# RS485_RS232_Sheet.net
KiCad netlist of a schematic drawn in Altium Designer
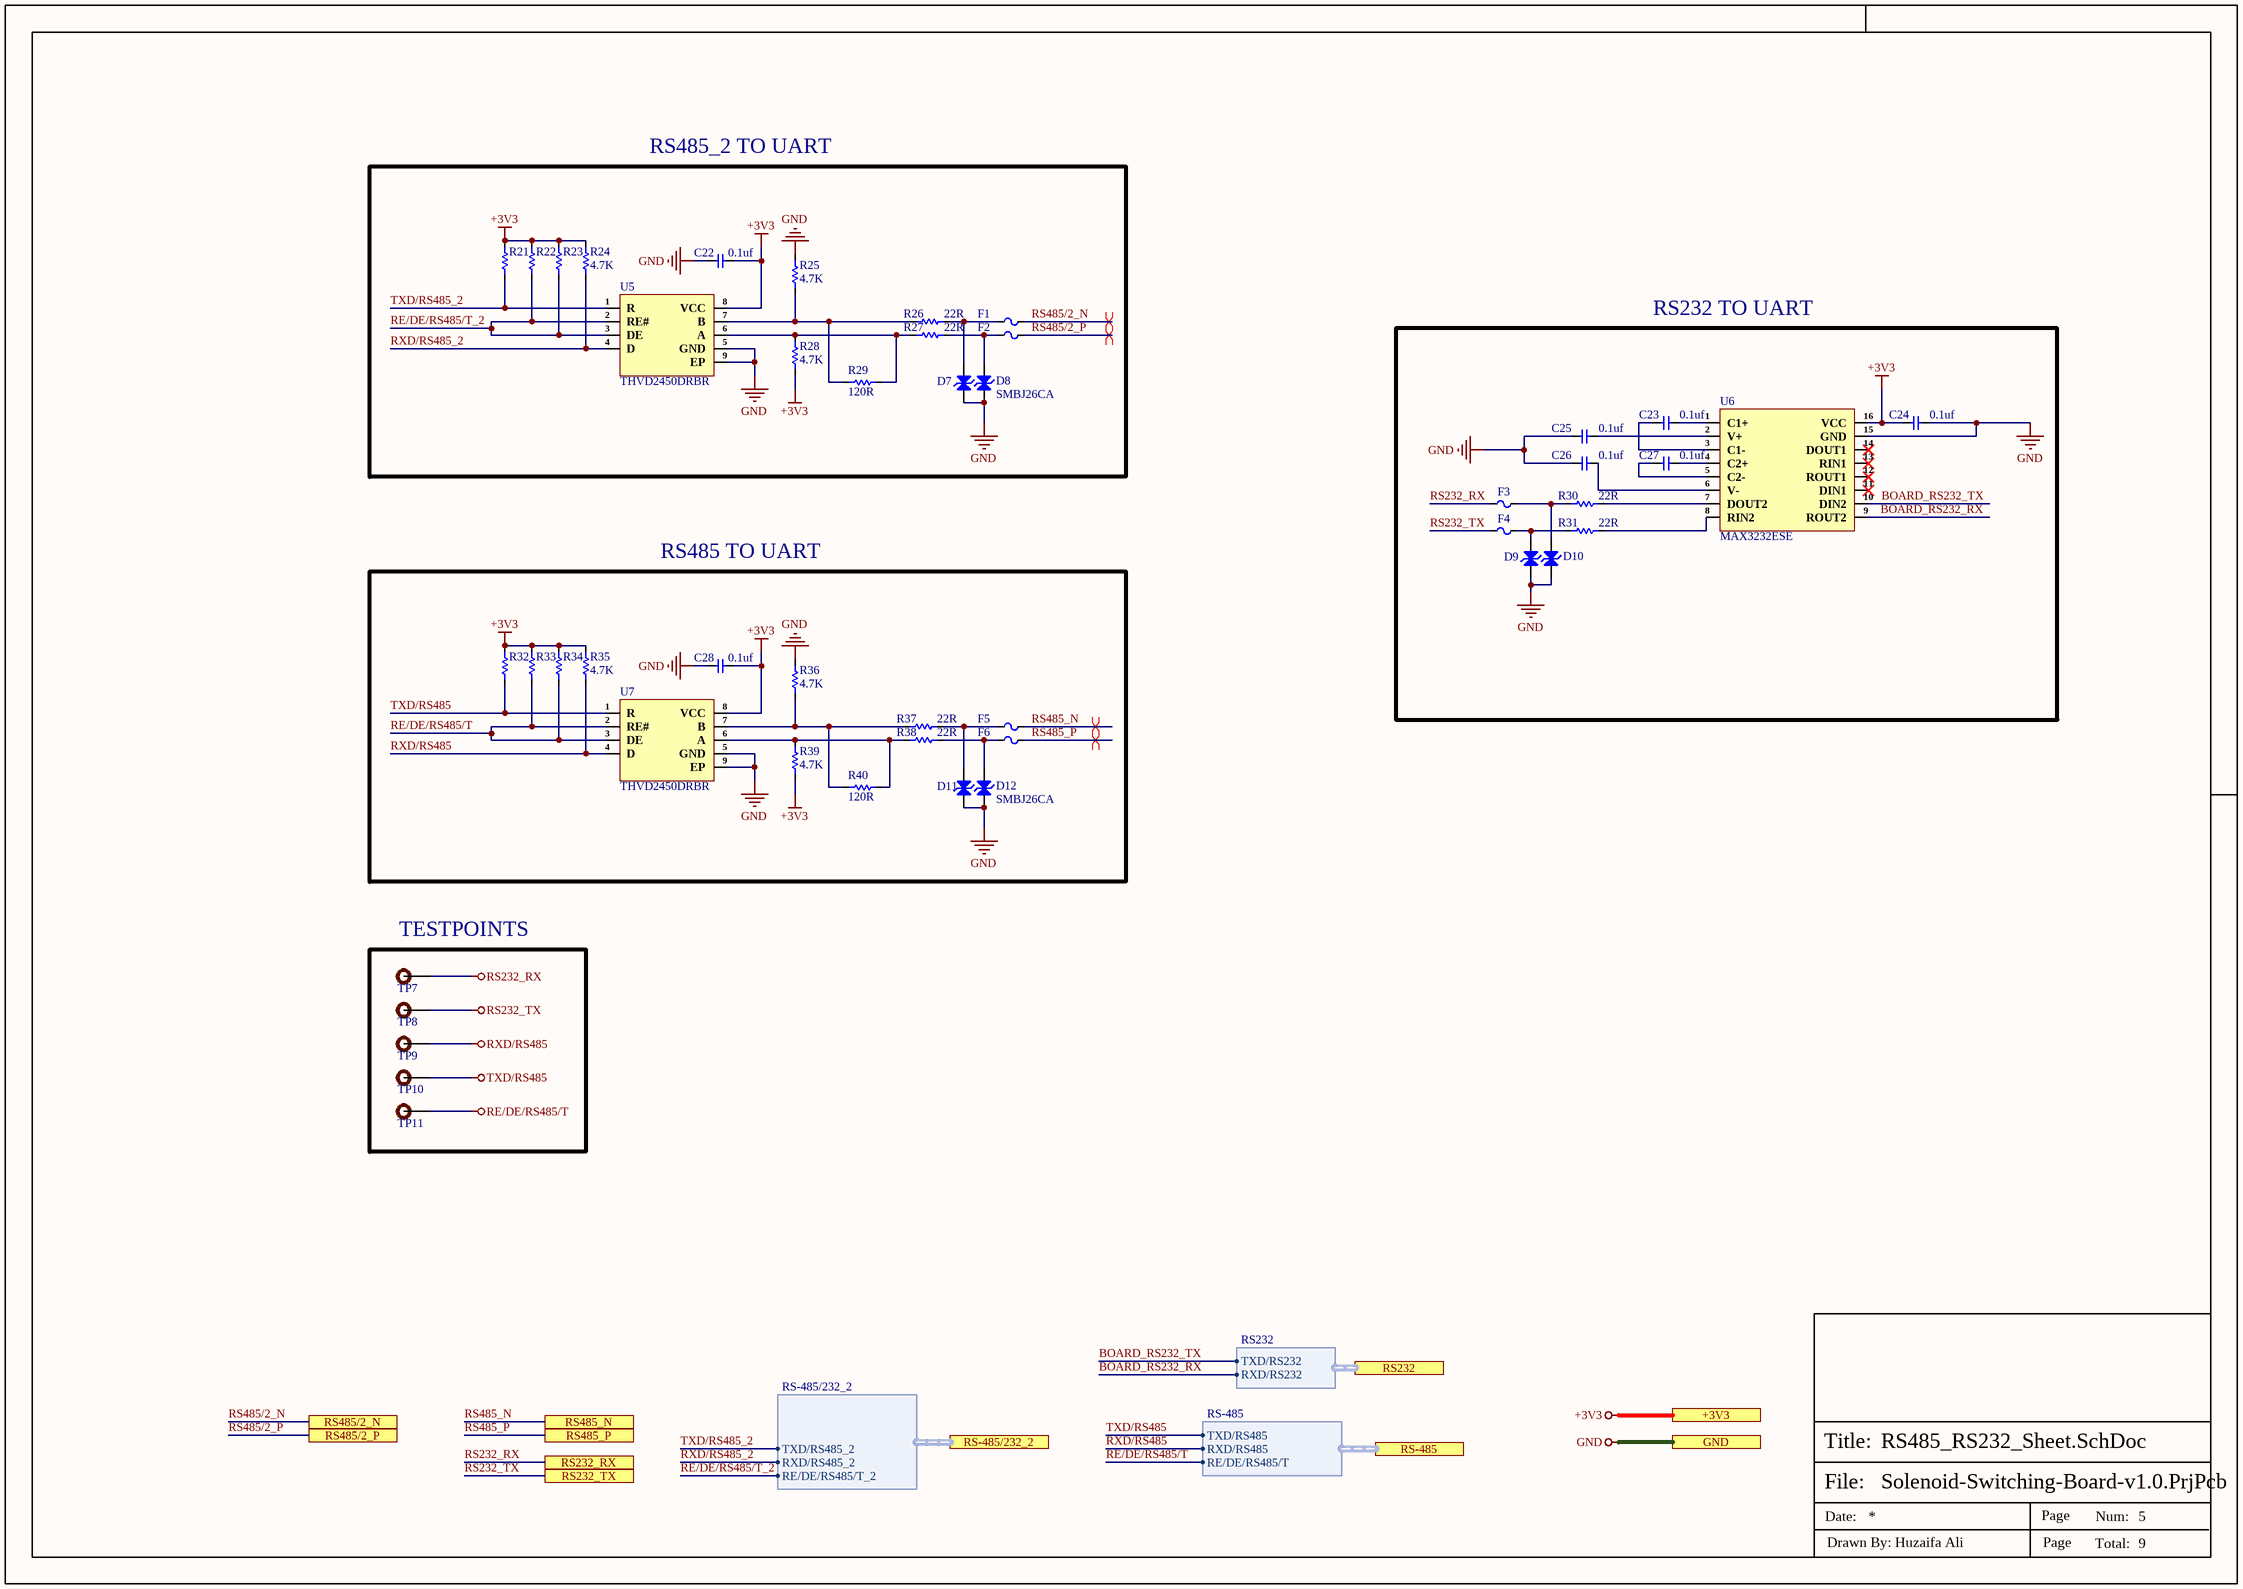
[diagram p0: RS485_RS232_Sheet.SchDoc]

(export (version "E")
  (design (tool "Eeschema 10.0.6"))
  (components
    (comp (ref "C22")
      (value "0.1uf")
      (footprint "Cap-0402")
      (description "CAP CER 0.1UF 100V X5R 0402")
      (fields
        (field (name "MANUFACTURER") "Murata")
        (field (name "MANUFACTURER PART NUMBER") "GRM155R62A104KE14D")
      )
      (libsource (lib "eSpark Libraries") (part "GRM155R62A104KE14D"))
    )
    (comp (ref "C23")
      (value "0.1uf")
      (footprint "Cap-0402")
      (description "CAP CER 0.1UF 100V X5R 0402")
      (fields
        (field (name "MANUFACTURER") "Murata")
        (field (name "MANUFACTURER PART NUMBER") "GRM155R62A104KE14D")
      )
      (libsource (lib "eSpark Libraries") (part "GRM155R62A104KE14D"))
    )
    (comp (ref "C24")
      (value "0.1uf")
      (footprint "Cap-0402")
      (description "CAP CER 0.1UF 100V X5R 0402")
      (fields
        (field (name "MANUFACTURER") "Murata")
        (field (name "MANUFACTURER PART NUMBER") "GRM155R62A104KE14D")
      )
      (libsource (lib "eSpark Libraries") (part "GRM155R62A104KE14D"))
    )
    (comp (ref "C25")
      (value "0.1uf")
      (footprint "Cap-0402")
      (description "CAP CER 0.1UF 100V X5R 0402")
      (fields
        (field (name "MANUFACTURER") "Murata")
        (field (name "MANUFACTURER PART NUMBER") "GRM155R62A104KE14D")
      )
      (libsource (lib "eSpark Libraries") (part "GRM155R62A104KE14D"))
    )
    (comp (ref "C26")
      (value "0.1uf")
      (footprint "Cap-0402")
      (description "CAP CER 0.1UF 100V X5R 0402")
      (fields
        (field (name "MANUFACTURER") "Murata")
        (field (name "MANUFACTURER PART NUMBER") "GRM155R62A104KE14D")
      )
      (libsource (lib "eSpark Libraries") (part "GRM155R62A104KE14D"))
    )
    (comp (ref "C27")
      (value "0.1uf")
      (footprint "Cap-0402")
      (description "CAP CER 0.1UF 100V X5R 0402")
      (fields
        (field (name "MANUFACTURER") "Murata")
        (field (name "MANUFACTURER PART NUMBER") "GRM155R62A104KE14D")
      )
      (libsource (lib "eSpark Libraries") (part "GRM155R62A104KE14D"))
    )
    (comp (ref "C28")
      (value "0.1uf")
      (footprint "Cap-0402")
      (description "CAP CER 0.1UF 100V X5R 0402")
      (fields
        (field (name "MANUFACTURER") "Murata")
        (field (name "MANUFACTURER PART NUMBER") "GRM155R62A104KE14D")
      )
      (libsource (lib "eSpark Libraries") (part "GRM155R62A104KE14D"))
    )
    (comp (ref "D7")
      (value "SMBJ26CA")
      (footprint "SMB Bi Directional")
      (description "SMB(DO-214AA) TVS ROHS")
      (fields (field (name "MANUFACTURER") "MSKSEMI") (field (name "LCSC PART NUMBER") "C5331111"))
      (libsource (lib "eSpark Libraries") (part "SMBJ26CA"))
    )
    (comp (ref "D8")
      (value "SMBJ26CA")
      (footprint "SMB Bi Directional")
      (description "SMB(DO-214AA) TVS ROHS")
      (fields (field (name "MANUFACTURER") "MSKSEMI") (field (name "LCSC PART NUMBER") "C5331111"))
      (libsource (lib "eSpark Libraries") (part "SMBJ26CA"))
    )
    (comp (ref "D9")
      (value "SMBJ26CA")
      (footprint "SMB Bi Directional")
      (description "SMB(DO-214AA) TVS ROHS")
      (fields (field (name "MANUFACTURER") "MSKSEMI") (field (name "LCSC PART NUMBER") "C5331111"))
      (libsource (lib "eSpark Libraries") (part "SMBJ26CA"))
    )
    (comp (ref "D10")
      (value "SMBJ26CA")
      (footprint "SMB Bi Directional")
      (description "SMB(DO-214AA) TVS ROHS")
      (fields (field (name "MANUFACTURER") "MSKSEMI") (field (name "LCSC PART NUMBER") "C5331111"))
      (libsource (lib "eSpark Libraries") (part "SMBJ26CA"))
    )
    (comp (ref "D11")
      (value "SMBJ26CA")
      (footprint "SMB Bi Directional")
      (description "SMB(DO-214AA) TVS ROHS")
      (fields (field (name "MANUFACTURER") "MSKSEMI") (field (name "LCSC PART NUMBER") "C5331111"))
      (libsource (lib "eSpark Libraries") (part "SMBJ26CA"))
    )
    (comp (ref "D12")
      (value "SMBJ26CA")
      (footprint "SMB Bi Directional")
      (description "SMB(DO-214AA) TVS ROHS")
      (fields (field (name "MANUFACTURER") "MSKSEMI") (field (name "LCSC PART NUMBER") "C5331111"))
      (libsource (lib "eSpark Libraries") (part "SMBJ26CA"))
    )
    (comp (ref "F1")
      (value "SMD0805P020TF")
      (footprint "Fuse-0805")
      (description "9V 200mA 100A 500mA 0805 Resettable Fuses ROHS")
      (fields (field (name "MANUFACTURER") "RUILON") (field (name "LCSC PART NUMBER") "C20976"))
      (libsource (lib "eSpark_centralized_Library(2022)") (part "SMD0805P020TF"))
    )
    (comp (ref "F2")
      (value "SMD0805P020TF")
      (footprint "Fuse-0805")
      (description "9V 200mA 100A 500mA 0805 Resettable Fuses ROHS")
      (fields (field (name "MANUFACTURER") "RUILON") (field (name "LCSC PART NUMBER") "C20976"))
      (libsource (lib "eSpark_centralized_Library(2022)") (part "SMD0805P020TF"))
    )
    (comp (ref "F3")
      (value "SMD0805P020TF")
      (footprint "Fuse-0805")
      (description "9V 200mA 100A 500mA 0805 Resettable Fuses ROHS")
      (fields (field (name "MANUFACTURER") "RUILON") (field (name "LCSC PART NUMBER") "C20976"))
      (libsource (lib "eSpark Libraries") (part "SMD0805P020TF"))
    )
    (comp (ref "F4")
      (value "SMD0805P020TF")
      (footprint "Fuse-0805")
      (description "9V 200mA 100A 500mA 0805 Resettable Fuses ROHS")
      (fields (field (name "MANUFACTURER") "RUILON") (field (name "LCSC PART NUMBER") "C20976"))
      (libsource (lib "eSpark Libraries") (part "SMD0805P020TF"))
    )
    (comp (ref "F5")
      (value "SMD0805P020TF")
      (footprint "Fuse-0805")
      (description "9V 200mA 100A 500mA 0805 Resettable Fuses ROHS")
      (fields (field (name "MANUFACTURER") "RUILON") (field (name "LCSC PART NUMBER") "C20976"))
      (libsource (lib "eSpark_centralized_Library(2022)") (part "SMD0805P020TF"))
    )
    (comp (ref "F6")
      (value "SMD0805P020TF")
      (footprint "Fuse-0805")
      (description "9V 200mA 100A 500mA 0805 Resettable Fuses ROHS")
      (fields (field (name "MANUFACTURER") "RUILON") (field (name "LCSC PART NUMBER") "C20976"))
      (libsource (lib "eSpark_centralized_Library(2022)") (part "SMD0805P020TF"))
    )
    (comp (ref "R21")
      (value "4.7K")
      (footprint "Res-0402")
      (description "RES 4.7K OHM 1% 1/16W 0402")
      (fields
        (field (name "MANUFACTURER") "Yageo")
        (field (name "MANUFACTURER PART NUMBER") "RC0402FR-074K7L")
      )
      (libsource (lib "eSpark Libraries") (part "RC0402FR-074K7L"))
    )
    (comp (ref "R22")
      (value "4.7K")
      (footprint "Res-0402")
      (description "RES 4.7K OHM 1% 1/16W 0402")
      (fields
        (field (name "MANUFACTURER") "Yageo")
        (field (name "MANUFACTURER PART NUMBER") "RC0402FR-074K7L")
      )
      (libsource (lib "eSpark Libraries") (part "RC0402FR-074K7L"))
    )
    (comp (ref "R23")
      (value "4.7K")
      (footprint "Res-0402")
      (description "RES 4.7K OHM 1% 1/16W 0402")
      (fields
        (field (name "MANUFACTURER") "Yageo")
        (field (name "MANUFACTURER PART NUMBER") "RC0402FR-074K7L")
      )
      (libsource (lib "eSpark Libraries") (part "RC0402FR-074K7L"))
    )
    (comp (ref "R24")
      (value "4.7K")
      (footprint "Res-0402")
      (description "RES 4.7K OHM 1% 1/16W 0402")
      (fields
        (field (name "MANUFACTURER") "Yageo")
        (field (name "MANUFACTURER PART NUMBER") "RC0402FR-074K7L")
      )
      (libsource (lib "eSpark Libraries") (part "RC0402FR-074K7L"))
    )
    (comp (ref "R25")
      (value "4.7K")
      (footprint "Res-0402")
      (description "RES 4.7K OHM 1% 1/16W 0402")
      (fields
        (field (name "MANUFACTURER") "Yageo")
        (field (name "MANUFACTURER PART NUMBER") "RC0402FR-074K7L")
      )
      (libsource (lib "eSpark Libraries") (part "RC0402FR-074K7L"))
    )
    (comp (ref "R26")
      (value "22R")
      (footprint "Res-0201")
      (description "RES 22 OHM 1% 1/20W 0201")
      (fields
        (field (name "MANUFACTURER") "Yageo")
        (field (name "MANUFACTURER PART NUMBER") "RC0201FR-0722RL")
      )
      (libsource (lib "eSpark Libraries") (part "RC0201FR-0722RL"))
    )
    (comp (ref "R27")
      (value "22R")
      (footprint "Res-0201")
      (description "RES 22 OHM 1% 1/20W 0201")
      (fields
        (field (name "MANUFACTURER") "Yageo")
        (field (name "MANUFACTURER PART NUMBER") "RC0201FR-0722RL")
      )
      (libsource (lib "eSpark Libraries") (part "RC0201FR-0722RL"))
    )
    (comp (ref "R28")
      (value "4.7K")
      (footprint "Res-0402")
      (description "RES 4.7K OHM 1% 1/16W 0402")
      (fields
        (field (name "MANUFACTURER") "Yageo")
        (field (name "MANUFACTURER PART NUMBER") "RC0402FR-074K7L")
      )
      (libsource (lib "eSpark Libraries") (part "RC0402FR-074K7L"))
    )
    (comp (ref "R29")
      (value "120R")
      (footprint "Res-0603")
      (description "RES 120 OHM 5% 1/10W 0603")
      (fields
        (field (name "MANUFACTURER") "Yageo")
        (field (name "MANUFACTURER PART NUMBER") "RC0603JR-07120RL")
      )
      (libsource (lib "eSpark Libraries") (part "RC0603JR-07120RL"))
    )
    (comp (ref "R30")
      (value "22R")
      (footprint "Res-0201")
      (description "RES 22 OHM 1% 1/20W 0201")
      (fields
        (field (name "MANUFACTURER") "Yageo")
        (field (name "MANUFACTURER PART NUMBER") "RC0201FR-0722RL")
      )
      (libsource (lib "eSpark Libraries") (part "RC0201FR-0722RL"))
    )
    (comp (ref "R31")
      (value "22R")
      (footprint "Res-0201")
      (description "RES 22 OHM 1% 1/20W 0201")
      (fields
        (field (name "MANUFACTURER") "Yageo")
        (field (name "MANUFACTURER PART NUMBER") "RC0201FR-0722RL")
      )
      (libsource (lib "eSpark Libraries") (part "RC0201FR-0722RL"))
    )
    (comp (ref "R32")
      (value "4.7K")
      (footprint "Res-0402")
      (description "RES 4.7K OHM 1% 1/16W 0402")
      (fields
        (field (name "MANUFACTURER") "Yageo")
        (field (name "MANUFACTURER PART NUMBER") "RC0402FR-074K7L")
      )
      (libsource (lib "eSpark Libraries") (part "RC0402FR-074K7L"))
    )
    (comp (ref "R33")
      (value "4.7K")
      (footprint "Res-0402")
      (description "RES 4.7K OHM 1% 1/16W 0402")
      (fields
        (field (name "MANUFACTURER") "Yageo")
        (field (name "MANUFACTURER PART NUMBER") "RC0402FR-074K7L")
      )
      (libsource (lib "eSpark Libraries") (part "RC0402FR-074K7L"))
    )
    (comp (ref "R34")
      (value "4.7K")
      (footprint "Res-0402")
      (description "RES 4.7K OHM 1% 1/16W 0402")
      (fields
        (field (name "MANUFACTURER") "Yageo")
        (field (name "MANUFACTURER PART NUMBER") "RC0402FR-074K7L")
      )
      (libsource (lib "eSpark Libraries") (part "RC0402FR-074K7L"))
    )
    (comp (ref "R35")
      (value "4.7K")
      (footprint "Res-0402")
      (description "RES 4.7K OHM 1% 1/16W 0402")
      (fields
        (field (name "MANUFACTURER") "Yageo")
        (field (name "MANUFACTURER PART NUMBER") "RC0402FR-074K7L")
      )
      (libsource (lib "eSpark Libraries") (part "RC0402FR-074K7L"))
    )
    (comp (ref "R36")
      (value "4.7K")
      (footprint "Res-0402")
      (description "RES 4.7K OHM 1% 1/16W 0402")
      (fields
        (field (name "MANUFACTURER") "Yageo")
        (field (name "MANUFACTURER PART NUMBER") "RC0402FR-074K7L")
      )
      (libsource (lib "eSpark Libraries") (part "RC0402FR-074K7L"))
    )
    (comp (ref "R37")
      (value "22R")
      (footprint "Res-0201")
      (description "RES 22 OHM 1% 1/20W 0201")
      (fields
        (field (name "MANUFACTURER") "Yageo")
        (field (name "MANUFACTURER PART NUMBER") "RC0201FR-0722RL")
      )
      (libsource (lib "eSpark Libraries") (part "RC0201FR-0722RL"))
    )
    (comp (ref "R38")
      (value "22R")
      (footprint "Res-0201")
      (description "RES 22 OHM 1% 1/20W 0201")
      (fields
        (field (name "MANUFACTURER") "Yageo")
        (field (name "MANUFACTURER PART NUMBER") "RC0201FR-0722RL")
      )
      (libsource (lib "eSpark Libraries") (part "RC0201FR-0722RL"))
    )
    (comp (ref "R39")
      (value "4.7K")
      (footprint "Res-0402")
      (description "RES 4.7K OHM 1% 1/16W 0402")
      (fields
        (field (name "MANUFACTURER") "Yageo")
        (field (name "MANUFACTURER PART NUMBER") "RC0402FR-074K7L")
      )
      (libsource (lib "eSpark Libraries") (part "RC0402FR-074K7L"))
    )
    (comp (ref "R40")
      (value "120R")
      (footprint "Res-0603")
      (description "RES 120 OHM 5% 1/10W 0603")
      (fields
        (field (name "MANUFACTURER") "Yageo")
        (field (name "MANUFACTURER PART NUMBER") "RC0603JR-07120RL")
      )
      (libsource (lib "eSpark Libraries") (part "RC0603JR-07120RL"))
    )
    (comp (ref "TP7")
      (value "TEST POINT")
      (footprint "Test-point")
      (description "Test Point ON")
      (libsource (lib "eSpark Libraries") (part "TEST POINT"))
    )
    (comp (ref "TP8")
      (value "TEST POINT")
      (footprint "Test-point")
      (description "Test Point ON")
      (libsource (lib "eSpark Libraries") (part "TEST POINT"))
    )
    (comp (ref "TP9")
      (value "TEST POINT")
      (footprint "Test-point")
      (description "Test Point ON")
      (libsource (lib "eSpark Libraries") (part "TEST POINT"))
    )
    (comp (ref "TP10")
      (value "TEST POINT")
      (footprint "Test-point")
      (description "Test Point ON")
      (libsource (lib "eSpark Libraries") (part "TEST POINT"))
    )
    (comp (ref "TP11")
      (value "TEST POINT")
      (footprint "Test-point")
      (description "Test Point ON")
      (libsource (lib "eSpark Libraries") (part "TEST POINT"))
    )
    (comp (ref "U5")
      (value "THVD2450DRBR")
      (footprint "SON-8-EP(3x3)")
      (description "IC TRANSCEIVER HALF 1/1 8SON")
      (fields (field (name "MANUFACTURER") "Texas Instruments") (field (name "LCSC PART NUMBER") "C2878080"))
      (libsource (lib "eSpark Libraries") (part "THVD2450DRBR"))
    )
    (comp (ref "U6")
      (value "MAX3232ESE")
      (footprint "SOP-16")
      (description "250Kbps transceiver 2/2 SOP-16 RS232 ICs ROHS")
      (fields (field (name "MANUFACTURER") "UMW") (field (name "LCSC PART NUMBER") "C2904738"))
      (libsource (lib "eSpark Libraries") (part "MAX3232ESE"))
    )
    (comp (ref "U7")
      (value "THVD2450DRBR")
      (footprint "SON-8-EP(3x3)")
      (description "IC TRANSCEIVER HALF 1/1 8SON")
      (fields (field (name "MANUFACTURER") "Texas Instruments") (field (name "LCSC PART NUMBER") "C2878080"))
      (libsource (lib "eSpark Libraries") (part "THVD2450DRBR"))
    )
  )
  (nets
    (net (code "4") (name "+3V3") (class "Default")
      (node (ref "C22") (pin "2") (pinfunction "2_2") (pintype "passive"))
      (node (ref "C24") (pin "2") (pinfunction "2_2") (pintype "passive"))
      (node (ref "C28") (pin "2") (pinfunction "2_2") (pintype "passive"))
      (node (ref "R21") (pin "2") (pinfunction "2_2") (pintype "passive"))
      (node (ref "R22") (pin "2") (pinfunction "2_2") (pintype "passive"))
      (node (ref "R23") (pin "2") (pinfunction "2_2") (pintype "passive"))
      (node (ref "R24") (pin "2") (pinfunction "2_2") (pintype "passive"))
      (node (ref "R28") (pin "1") (pinfunction "1_1") (pintype "passive"))
      (node (ref "R32") (pin "2") (pinfunction "2_2") (pintype "passive"))
      (node (ref "R33") (pin "2") (pinfunction "2_2") (pintype "passive"))
      (node (ref "R34") (pin "2") (pinfunction "2_2") (pintype "passive"))
      (node (ref "R35") (pin "2") (pinfunction "2_2") (pintype "passive"))
      (node (ref "R39") (pin "1") (pinfunction "1_1") (pintype "passive"))
      (node (ref "U5") (pin "8") (pinfunction "VCC_8") (pintype "passive"))
      (node (ref "U6") (pin "16") (pinfunction "VCC_16") (pintype "passive"))
      (node (ref "U7") (pin "8") (pinfunction "VCC_8") (pintype "passive"))
    )
    (net (code "5") (name "/BOARD_RS232_RX") (class "Default")
      (node (ref "U6") (pin "9") (pinfunction "ROUT2_9") (pintype "passive"))
    )
    (net (code "6") (name "/BOARD_RS232_TX") (class "Default")
      (node (ref "U6") (pin "10") (pinfunction "DIN2_10") (pintype "passive"))
    )
    (net (code "7") (name "/RE{slash}DE{slash}RS485{slash}T_2") (class "Default")
      (node (ref "R22") (pin "1") (pinfunction "1_1") (pintype "passive"))
      (node (ref "R23") (pin "1") (pinfunction "1_1") (pintype "passive"))
      (node (ref "U5") (pin "2") (pinfunction "RE#_2") (pintype "passive"))
      (node (ref "U5") (pin "3") (pinfunction "DE_3") (pintype "passive"))
    )
    (net (code "8") (name "/RS485_N") (class "Default")
      (node (ref "F5") (pin "2") (pinfunction "2_2") (pintype "passive"))
    )
    (net (code "9") (name "/RS485_P") (class "Default")
      (node (ref "F6") (pin "2") (pinfunction "2_2") (pintype "passive"))
    )
    (net (code "10") (name "/RS485{slash}2_N") (class "Default")
      (node (ref "F1") (pin "2") (pinfunction "2_2") (pintype "passive"))
    )
    (net (code "11") (name "/RS485{slash}2_P") (class "Default")
      (node (ref "F2") (pin "2") (pinfunction "2_2") (pintype "passive"))
    )
    (net (code "12") (name "/RXD{slash}RS485_2") (class "Default")
      (node (ref "R24") (pin "1") (pinfunction "1_1") (pintype "passive"))
      (node (ref "U5") (pin "4") (pinfunction "D_4") (pintype "passive"))
    )
    (net (code "13") (name "/TXD{slash}RS485_2") (class "Default")
      (node (ref "R21") (pin "1") (pinfunction "1_1") (pintype "passive"))
      (node (ref "U5") (pin "1") (pinfunction "R_1") (pintype "passive"))
    )
    (net (code "17") (name "GND") (class "Default")
      (node (ref "C22") (pin "1") (pinfunction "1_1") (pintype "passive"))
      (node (ref "C24") (pin "1") (pinfunction "1_1") (pintype "passive"))
      (node (ref "C25") (pin "1") (pinfunction "1_1") (pintype "passive"))
      (node (ref "C26") (pin "1") (pinfunction "1_1") (pintype "passive"))
      (node (ref "C28") (pin "1") (pinfunction "1_1") (pintype "passive"))
      (node (ref "D10") (pin "1") (pinfunction "A_1") (pintype "passive"))
      (node (ref "D11") (pin "1") (pinfunction "A_1") (pintype "passive"))
      (node (ref "D12") (pin "1") (pinfunction "A_1") (pintype "passive"))
      (node (ref "D7") (pin "1") (pinfunction "A_1") (pintype "passive"))
      (node (ref "D8") (pin "1") (pinfunction "A_1") (pintype "passive"))
      (node (ref "D9") (pin "1") (pinfunction "A_1") (pintype "passive"))
      (node (ref "R25") (pin "2") (pinfunction "2_2") (pintype "passive"))
      (node (ref "R36") (pin "2") (pinfunction "2_2") (pintype "passive"))
      (node (ref "U5") (pin "5") (pinfunction "GND_5") (pintype "passive"))
      (node (ref "U5") (pin "9") (pinfunction "EP_9") (pintype "passive"))
      (node (ref "U6") (pin "15") (pinfunction "GND_15") (pintype "passive"))
      (node (ref "U7") (pin "5") (pinfunction "GND_5") (pintype "passive"))
      (node (ref "U7") (pin "9") (pinfunction "EP_9") (pintype "passive"))
    )
    (net (code "18") (name "Net-(D7-K)") (class "Default")
      (node (ref "D7") (pin "2") (pinfunction "K_2") (pintype "passive"))
      (node (ref "F1") (pin "1") (pinfunction "1_1") (pintype "passive"))
      (node (ref "R26") (pin "2") (pinfunction "2_2") (pintype "passive"))
    )
    (net (code "19") (name "Net-(D8-K)") (class "Default")
      (node (ref "D8") (pin "2") (pinfunction "K_2") (pintype "passive"))
      (node (ref "F2") (pin "1") (pinfunction "1_1") (pintype "passive"))
      (node (ref "R27") (pin "2") (pinfunction "2_2") (pintype "passive"))
    )
    (net (code "20") (name "Net-(D9-K)") (class "Default")
      (node (ref "D9") (pin "2") (pinfunction "K_2") (pintype "passive"))
      (node (ref "F4") (pin "2") (pinfunction "2_2") (pintype "passive"))
      (node (ref "R31") (pin "1") (pinfunction "1_1") (pintype "passive"))
    )
    (net (code "21") (name "Net-(D10-K)") (class "Default")
      (node (ref "D10") (pin "2") (pinfunction "K_2") (pintype "passive"))
      (node (ref "F3") (pin "2") (pinfunction "2_2") (pintype "passive"))
      (node (ref "R30") (pin "1") (pinfunction "1_1") (pintype "passive"))
    )
    (net (code "22") (name "Net-(D11-K)") (class "Default")
      (node (ref "D11") (pin "2") (pinfunction "K_2") (pintype "passive"))
      (node (ref "F5") (pin "1") (pinfunction "1_1") (pintype "passive"))
      (node (ref "R37") (pin "2") (pinfunction "2_2") (pintype "passive"))
    )
    (net (code "23") (name "Net-(D12-K)") (class "Default")
      (node (ref "D12") (pin "2") (pinfunction "K_2") (pintype "passive"))
      (node (ref "F6") (pin "1") (pinfunction "1_1") (pintype "passive"))
      (node (ref "R38") (pin "2") (pinfunction "2_2") (pintype "passive"))
    )
    (net (code "24") (name "Net-(U5-A)") (class "Default")
      (node (ref "R27") (pin "1") (pinfunction "1_1") (pintype "passive"))
      (node (ref "R28") (pin "2") (pinfunction "2_2") (pintype "passive"))
      (node (ref "R29") (pin "2") (pinfunction "2_2") (pintype "passive"))
      (node (ref "U5") (pin "6") (pinfunction "A_6") (pintype "passive"))
    )
    (net (code "25") (name "Net-(U5-B)") (class "Default")
      (node (ref "R25") (pin "1") (pinfunction "1_1") (pintype "passive"))
      (node (ref "R26") (pin "1") (pinfunction "1_1") (pintype "passive"))
      (node (ref "R29") (pin "1") (pinfunction "1_1") (pintype "passive"))
      (node (ref "U5") (pin "7") (pinfunction "B_7") (pintype "passive"))
    )
    (net (code "26") (name "Net-(U6-C1+)") (class "Default")
      (node (ref "C23") (pin "1") (pinfunction "1_1") (pintype "passive"))
      (node (ref "U6") (pin "1") (pinfunction "C1+_1") (pintype "passive"))
    )
    (net (code "27") (name "Net-(U6-C1-)") (class "Default")
      (node (ref "C23") (pin "2") (pinfunction "2_2") (pintype "passive"))
      (node (ref "U6") (pin "3") (pinfunction "C1-_3") (pintype "passive"))
    )
    (net (code "28") (name "Net-(U6-C2+)") (class "Default")
      (node (ref "C27") (pin "1") (pinfunction "1_1") (pintype "passive"))
      (node (ref "U6") (pin "4") (pinfunction "C2+_4") (pintype "passive"))
    )
    (net (code "29") (name "Net-(U6-C2-)") (class "Default")
      (node (ref "C27") (pin "2") (pinfunction "2_2") (pintype "passive"))
      (node (ref "U6") (pin "5") (pinfunction "C2-_5") (pintype "passive"))
    )
    (net (code "30") (name "Net-(U6-DOUT2)") (class "Default")
      (node (ref "R30") (pin "2") (pinfunction "2_2") (pintype "passive"))
      (node (ref "U6") (pin "7") (pinfunction "DOUT2_7") (pintype "passive"))
    )
    (net (code "31") (name "Net-(U6-RIN2)") (class "Default")
      (node (ref "R31") (pin "2") (pinfunction "2_2") (pintype "passive"))
      (node (ref "U6") (pin "8") (pinfunction "RIN2_8") (pintype "passive"))
    )
    (net (code "32") (name "Net-(U6-V+)") (class "Default")
      (node (ref "C25") (pin "2") (pinfunction "2_2") (pintype "passive"))
      (node (ref "U6") (pin "2") (pinfunction "V+_2") (pintype "passive"))
    )
    (net (code "33") (name "Net-(U6-V-)") (class "Default")
      (node (ref "C26") (pin "2") (pinfunction "2_2") (pintype "passive"))
      (node (ref "U6") (pin "6") (pinfunction "V-_6") (pintype "passive"))
    )
    (net (code "34") (name "Net-(U7-A)") (class "Default")
      (node (ref "R38") (pin "1") (pinfunction "1_1") (pintype "passive"))
      (node (ref "R39") (pin "2") (pinfunction "2_2") (pintype "passive"))
      (node (ref "R40") (pin "2") (pinfunction "2_2") (pintype "passive"))
      (node (ref "U7") (pin "6") (pinfunction "A_6") (pintype "passive"))
    )
    (net (code "35") (name "Net-(U7-B)") (class "Default")
      (node (ref "R36") (pin "1") (pinfunction "1_1") (pintype "passive"))
      (node (ref "R37") (pin "1") (pinfunction "1_1") (pintype "passive"))
      (node (ref "R40") (pin "1") (pinfunction "1_1") (pintype "passive"))
      (node (ref "U7") (pin "7") (pinfunction "B_7") (pintype "passive"))
    )
    (net (code "36") (name "RE{slash}DE{slash}RS485{slash}T") (class "Default")
      (node (ref "R33") (pin "1") (pinfunction "1_1") (pintype "passive"))
      (node (ref "R34") (pin "1") (pinfunction "1_1") (pintype "passive"))
      (node (ref "TP11") (pin "1") (pinfunction "1_1") (pintype "passive"))
      (node (ref "U7") (pin "2") (pinfunction "RE#_2") (pintype "passive"))
      (node (ref "U7") (pin "3") (pinfunction "DE_3") (pintype "passive"))
    )
    (net (code "37") (name "RS232_RX") (class "Default")
      (node (ref "F3") (pin "1") (pinfunction "1_1") (pintype "passive"))
      (node (ref "TP7") (pin "1") (pinfunction "1_1") (pintype "passive"))
    )
    (net (code "38") (name "RS232_TX") (class "Default")
      (node (ref "F4") (pin "1") (pinfunction "1_1") (pintype "passive"))
      (node (ref "TP8") (pin "1") (pinfunction "1_1") (pintype "passive"))
    )
    (net (code "39") (name "RXD{slash}RS485") (class "Default")
      (node (ref "R35") (pin "1") (pinfunction "1_1") (pintype "passive"))
      (node (ref "TP9") (pin "1") (pinfunction "1_1") (pintype "passive"))
      (node (ref "U7") (pin "4") (pinfunction "D_4") (pintype "passive"))
    )
    (net (code "40") (name "TXD{slash}RS485") (class "Default")
      (node (ref "R32") (pin "1") (pinfunction "1_1") (pintype "passive"))
      (node (ref "TP10") (pin "1") (pinfunction "1_1") (pintype "passive"))
      (node (ref "U7") (pin "1") (pinfunction "R_1") (pintype "passive"))
    )
    (net (code "41") (name "unconnected-(U6-DIN1-Pad11)") (class "Default")
      (node (ref "U6") (pin "11") (pinfunction "DIN1_11") (pintype "passive+no_connect"))
    )
    (net (code "42") (name "unconnected-(U6-DOUT1-Pad14)") (class "Default")
      (node (ref "U6") (pin "14") (pinfunction "DOUT1_14") (pintype "passive+no_connect"))
    )
    (net (code "43") (name "unconnected-(U6-RIN1-Pad13)") (class "Default")
      (node (ref "U6") (pin "13") (pinfunction "RIN1_13") (pintype "passive+no_connect"))
    )
    (net (code "44") (name "unconnected-(U6-ROUT1-Pad12)") (class "Default")
      (node (ref "U6") (pin "12") (pinfunction "ROUT1_12") (pintype "passive+no_connect"))
    )
  )
)
